# TDA2040_Amp_v1_4.net
KiCad netlist of a schematic drawn in EAGLE
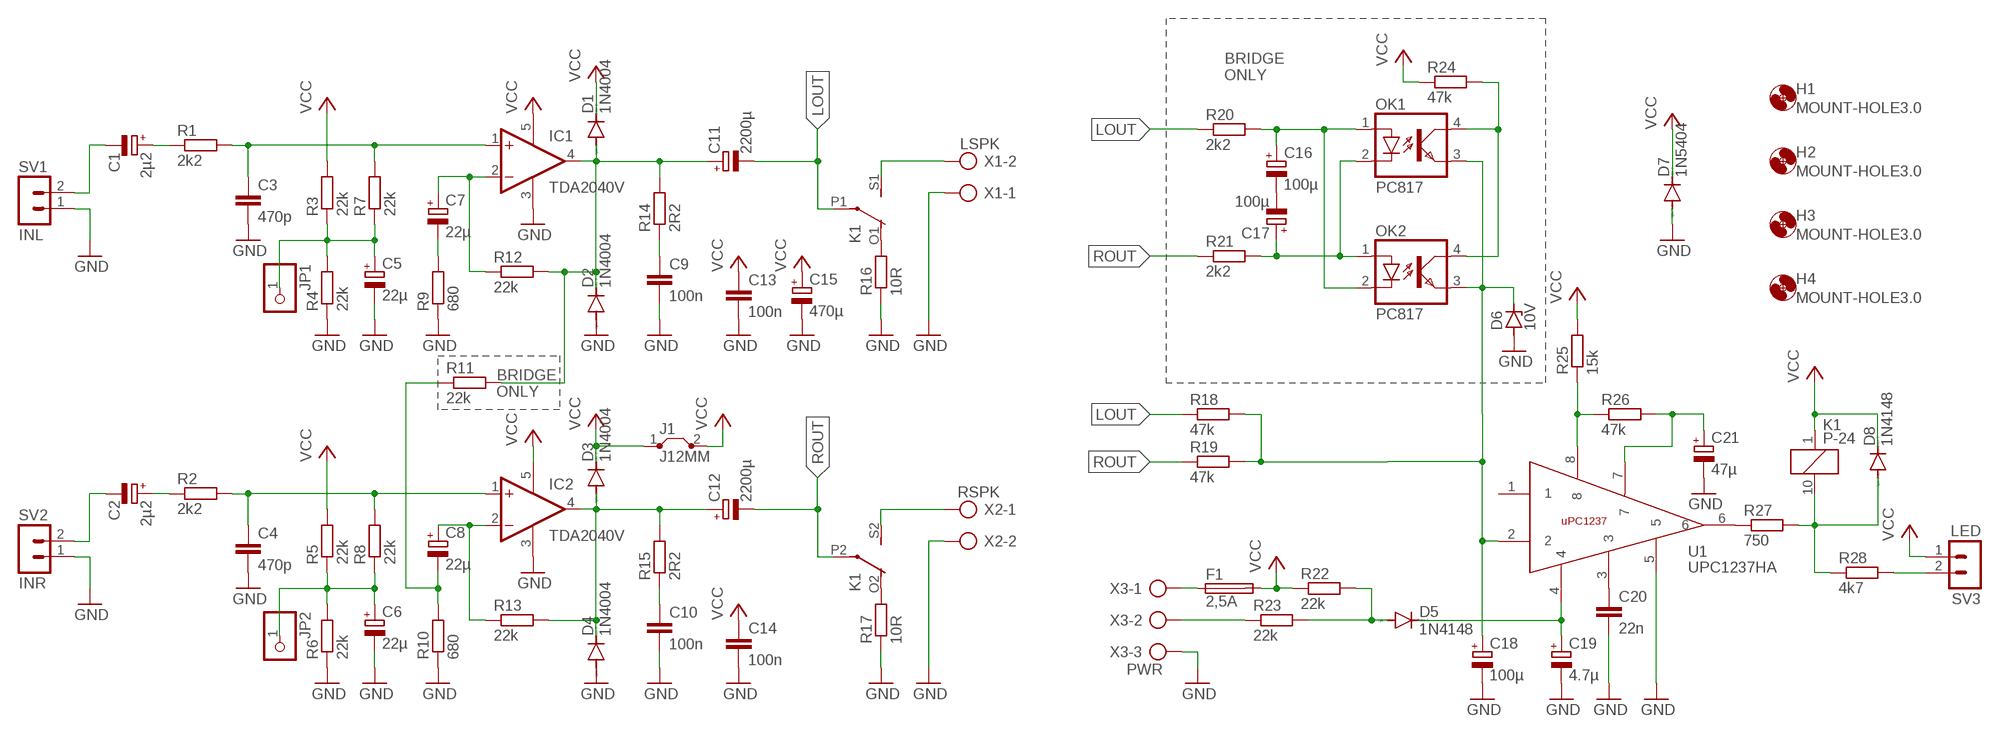
[diagram p0: schematic, sheet 1]

(export (version "E")
  (design (tool "Eeschema 10.0.6"))
  (components
    (comp (ref "C1")
      (value "2µ2")
      (footprint "eagle-import:E2,5-5")
      (libsource (lib "eagle-import") (part "CPOL-EUE2.5-5"))
    )
    (comp (ref "C2")
      (value "2µ2")
      (footprint "eagle-import:E2,5-5")
      (libsource (lib "eagle-import") (part "CPOL-EUE2.5-5"))
    )
    (comp (ref "C3")
      (value "470p")
      (footprint "eagle-import:C050-024X044")
      (libsource (lib "eagle-import") (part "C-EU050-024X044"))
    )
    (comp (ref "C4")
      (value "470p")
      (footprint "eagle-import:C050-024X044")
      (libsource (lib "eagle-import") (part "C-EU050-024X044"))
    )
    (comp (ref "C5")
      (value "22µ")
      (footprint "eagle-import:E2,5-6")
      (libsource (lib "eagle-import") (part "CPOL-EUE2.5-6"))
    )
    (comp (ref "C6")
      (value "22µ")
      (footprint "eagle-import:E2,5-6")
      (libsource (lib "eagle-import") (part "CPOL-EUE2.5-6"))
    )
    (comp (ref "C7")
      (value "22µ")
      (footprint "eagle-import:E2,5-6")
      (libsource (lib "eagle-import") (part "CPOL-EUE2.5-6"))
    )
    (comp (ref "C8")
      (value "22µ")
      (footprint "eagle-import:E2,5-6")
      (libsource (lib "eagle-import") (part "CPOL-EUE2.5-6"))
    )
    (comp (ref "C9")
      (value "100n")
      (footprint "eagle-import:C050-024X044")
      (libsource (lib "eagle-import") (part "C-EU050-024X044"))
    )
    (comp (ref "C10")
      (value "100n")
      (footprint "eagle-import:C050-024X044")
      (libsource (lib "eagle-import") (part "C-EU050-024X044"))
    )
    (comp (ref "C11")
      (value "2200µ")
      (footprint "eagle-import:E5-13")
      (libsource (lib "eagle-import") (part "CPOL-EUE5-13"))
    )
    (comp (ref "C12")
      (value "2200µ")
      (footprint "eagle-import:E5-13")
      (libsource (lib "eagle-import") (part "CPOL-EUE5-13"))
    )
    (comp (ref "C13")
      (value "100n")
      (footprint "eagle-import:C050-024X044")
      (libsource (lib "eagle-import") (part "C-EU050-024X044"))
    )
    (comp (ref "C14")
      (value "100n")
      (footprint "eagle-import:C050-024X044")
      (libsource (lib "eagle-import") (part "C-EU050-024X044"))
    )
    (comp (ref "C15")
      (value "470µ")
      (footprint "eagle-import:E5-13")
      (libsource (lib "eagle-import") (part "CPOL-EUE5-13"))
    )
    (comp (ref "C16")
      (value "100µ")
      (footprint "eagle-import:E2,5-6")
      (libsource (lib "eagle-import") (part "CPOL-EUE2.5-6"))
    )
    (comp (ref "C17")
      (value "100µ")
      (footprint "eagle-import:E2,5-6")
      (libsource (lib "eagle-import") (part "CPOL-EUE2.5-6"))
    )
    (comp (ref "C18")
      (value "100µ")
      (footprint "eagle-import:E2,5-5")
      (libsource (lib "eagle-import") (part "CPOL-EUE2.5-5"))
    )
    (comp (ref "C19")
      (value "4.7µ")
      (footprint "eagle-import:E2,5-5")
      (libsource (lib "eagle-import") (part "CPOL-EUE2.5-5"))
    )
    (comp (ref "C20")
      (value "22n")
      (footprint "eagle-import:C050-024X044")
      (libsource (lib "eagle-import") (part "C-EU050-024X044"))
    )
    (comp (ref "C21")
      (value "47µ")
      (footprint "eagle-import:E2,5-5")
      (libsource (lib "eagle-import") (part "CPOL-EUE2.5-5"))
    )
    (comp (ref "D1")
      (value "1N4004")
      (footprint "eagle-import:DO41-10")
      (libsource (lib "eagle-import") (part "1N4004"))
    )
    (comp (ref "D2")
      (value "1N4004")
      (footprint "eagle-import:DO41-10")
      (libsource (lib "eagle-import") (part "1N4004"))
    )
    (comp (ref "D3")
      (value "1N4004")
      (footprint "eagle-import:DO41-10")
      (libsource (lib "eagle-import") (part "1N4004"))
    )
    (comp (ref "D4")
      (value "1N4004")
      (footprint "eagle-import:DO41-10")
      (libsource (lib "eagle-import") (part "1N4004"))
    )
    (comp (ref "D5")
      (value "1N4148")
      (footprint "eagle-import:DO35-7")
      (libsource (lib "eagle-import") (part "1N4148DO35-7"))
    )
    (comp (ref "D6")
      (value "10V")
      (footprint "eagle-import:DO34Z7")
      (libsource (lib "eagle-import") (part "ZENER-DIODEDO34-7"))
    )
    (comp (ref "D7")
      (value "1N5404")
      (footprint "eagle-import:DO201-15")
      (libsource (lib "eagle-import") (part "1N5400"))
    )
    (comp (ref "D8")
      (value "1N4148")
      (footprint "eagle-import:DO35-7")
      (libsource (lib "eagle-import") (part "1N4148DO35-7"))
    )
    (comp (ref "F1")
      (value "2,5A")
      (footprint "eagle-import:SH22")
      (libsource (lib "eagle-import") (part "SH22"))
    )
    (comp (ref "H1")
      (value "MOUNT-HOLE3.0")
      (footprint "eagle-import:3,0")
      (libsource (lib "eagle-import") (part "MOUNT-HOLE3.0"))
    )
    (comp (ref "H2")
      (value "MOUNT-HOLE3.0")
      (footprint "eagle-import:3,0")
      (libsource (lib "eagle-import") (part "MOUNT-HOLE3.0"))
    )
    (comp (ref "H3")
      (value "MOUNT-HOLE3.0")
      (footprint "eagle-import:3,0")
      (libsource (lib "eagle-import") (part "MOUNT-HOLE3.0"))
    )
    (comp (ref "H4")
      (value "MOUNT-HOLE3.0")
      (footprint "eagle-import:3,0")
      (libsource (lib "eagle-import") (part "MOUNT-HOLE3.0"))
    )
    (comp (ref "IC1")
      (value "TDA2040V")
      (footprint "eagle-import:CB360")
      (libsource (lib "eagle-import") (part "TDA2040V"))
    )
    (comp (ref "IC2")
      (value "TDA2040V")
      (footprint "eagle-import:CB360")
      (libsource (lib "eagle-import") (part "TDA2040V"))
    )
    (comp (ref "J1")
      (value "J12MM")
      (footprint "eagle-import:12")
      (libsource (lib "eagle-import") (part "J12MM"))
    )
    (comp (ref "JP1")
      (value "PINHD-1X1A")
      (footprint "eagle-import:1X01A")
      (libsource (lib "eagle-import") (part "PINHD-1X1A"))
    )
    (comp (ref "JP2")
      (value "PINHD-1X1A")
      (footprint "eagle-import:1X01A")
      (libsource (lib "eagle-import") (part "PINHD-1X1A"))
    )
    (comp (ref "K1")
      (value "P-24")
      (footprint "eagle-import:G6H2-100")
      (libsource (lib "eagle-import") (part "G6H2-100"))
    )
    (comp (ref "OK1")
      (value "PC817")
      (footprint "eagle-import:DIL04")
      (fields (field (name "MPN") "PC817X4J000F"))
      (libsource (lib "eagle-import") (part "PC817"))
    )
    (comp (ref "OK2")
      (value "PC817")
      (footprint "eagle-import:DIL04")
      (fields (field (name "MPN") "PC817X4J000F"))
      (libsource (lib "eagle-import") (part "PC817"))
    )
    (comp (ref "R1")
      (value "2k2")
      (footprint "eagle-import:0207_10")
      (libsource (lib "eagle-import") (part "R-EU_0207/10"))
    )
    (comp (ref "R2")
      (value "2k2")
      (footprint "eagle-import:0207_10")
      (libsource (lib "eagle-import") (part "R-EU_0207/10"))
    )
    (comp (ref "R3")
      (value "22k")
      (footprint "eagle-import:0207_10")
      (libsource (lib "eagle-import") (part "R-EU_0207/10"))
    )
    (comp (ref "R4")
      (value "22k")
      (footprint "eagle-import:0207_10")
      (libsource (lib "eagle-import") (part "R-EU_0207/10"))
    )
    (comp (ref "R5")
      (value "22k")
      (footprint "eagle-import:0207_10")
      (libsource (lib "eagle-import") (part "R-EU_0207/10"))
    )
    (comp (ref "R6")
      (value "22k")
      (footprint "eagle-import:0207_10")
      (libsource (lib "eagle-import") (part "R-EU_0207/10"))
    )
    (comp (ref "R7")
      (value "22k")
      (footprint "eagle-import:0207_10")
      (libsource (lib "eagle-import") (part "R-EU_0207/10"))
    )
    (comp (ref "R8")
      (value "22k")
      (footprint "eagle-import:0207_10")
      (libsource (lib "eagle-import") (part "R-EU_0207/10"))
    )
    (comp (ref "R9")
      (value "680")
      (footprint "eagle-import:0207_10")
      (libsource (lib "eagle-import") (part "R-EU_0207/10"))
    )
    (comp (ref "R10")
      (value "680")
      (footprint "eagle-import:0207_10")
      (libsource (lib "eagle-import") (part "R-EU_0207/10"))
    )
    (comp (ref "R11")
      (value "22k")
      (footprint "eagle-import:0207_10")
      (libsource (lib "eagle-import") (part "R-EU_0207/10"))
    )
    (comp (ref "R12")
      (value "22k")
      (footprint "eagle-import:0207_10")
      (libsource (lib "eagle-import") (part "R-EU_0207/10"))
    )
    (comp (ref "R13")
      (value "22k")
      (footprint "eagle-import:0207_10")
      (libsource (lib "eagle-import") (part "R-EU_0207/10"))
    )
    (comp (ref "R14")
      (value "2R2")
      (footprint "eagle-import:0207_10")
      (libsource (lib "eagle-import") (part "R-EU_0207/10"))
    )
    (comp (ref "R15")
      (value "2R2")
      (footprint "eagle-import:0207_10")
      (libsource (lib "eagle-import") (part "R-EU_0207/10"))
    )
    (comp (ref "R16")
      (value "10R")
      (footprint "eagle-import:0207_10")
      (libsource (lib "eagle-import") (part "R-EU_0207/10"))
    )
    (comp (ref "R17")
      (value "10R")
      (footprint "eagle-import:0207_10")
      (libsource (lib "eagle-import") (part "R-EU_0207/10"))
    )
    (comp (ref "R18")
      (value "47k")
      (footprint "eagle-import:0207_10")
      (libsource (lib "eagle-import") (part "R-EU_0207/10"))
    )
    (comp (ref "R19")
      (value "47k")
      (footprint "eagle-import:0207_10")
      (libsource (lib "eagle-import") (part "R-EU_0207/10"))
    )
    (comp (ref "R20")
      (value "2k2")
      (footprint "eagle-import:0207_10")
      (libsource (lib "eagle-import") (part "R-EU_0207/10"))
    )
    (comp (ref "R21")
      (value "2k2")
      (footprint "eagle-import:0207_10")
      (libsource (lib "eagle-import") (part "R-EU_0207/10"))
    )
    (comp (ref "R22")
      (value "22k")
      (footprint "eagle-import:0207_10")
      (libsource (lib "eagle-import") (part "R-EU_0207/10"))
    )
    (comp (ref "R23")
      (value "22k")
      (footprint "eagle-import:0207_10")
      (libsource (lib "eagle-import") (part "R-EU_0207/10"))
    )
    (comp (ref "R24")
      (value "47k")
      (footprint "eagle-import:0207_10")
      (libsource (lib "eagle-import") (part "R-EU_0207/10"))
    )
    (comp (ref "R25")
      (value "15k")
      (footprint "eagle-import:0207_10")
      (libsource (lib "eagle-import") (part "R-EU_0207/10"))
    )
    (comp (ref "R26")
      (value "47k")
      (footprint "eagle-import:0207_10")
      (libsource (lib "eagle-import") (part "R-EU_0207/10"))
    )
    (comp (ref "R27")
      (value "750")
      (footprint "eagle-import:0207_10")
      (libsource (lib "eagle-import") (part "R-EU_0207/10"))
    )
    (comp (ref "R28")
      (value "4k7")
      (footprint "eagle-import:0207_10")
      (libsource (lib "eagle-import") (part "R-EU_0207/10"))
    )
    (comp (ref "SV1")
      (value "INL")
      (footprint "eagle-import:MA02-1")
      (libsource (lib "eagle-import") (part "MA02-1"))
    )
    (comp (ref "SV2")
      (value "INR")
      (footprint "eagle-import:MA02-1")
      (libsource (lib "eagle-import") (part "MA02-1"))
    )
    (comp (ref "SV3")
      (value "LED")
      (footprint "eagle-import:MA02-1")
      (libsource (lib "eagle-import") (part "MA02-1"))
    )
    (comp (ref "U1")
      (value "UPC1237HA")
      (footprint "eagle-import:SIP8")
      (fields (field (name "MF") "NEC"))
      (libsource (lib "eagle-import") (part "UPC1237HA"))
    )
    (comp (ref "X1")
      (value "LSPK")
      (footprint "eagle-import:AK500_2")
      (libsource (lib "eagle-import") (part "AK500/2"))
    )
    (comp (ref "X2")
      (value "RSPK")
      (footprint "eagle-import:AK500_2")
      (libsource (lib "eagle-import") (part "AK500/2"))
    )
    (comp (ref "X3")
      (value "PWR")
      (footprint "eagle-import:AK500_3")
      (libsource (lib "eagle-import") (part "AK500/3"))
    )
  )
  (nets
    (net (code "1") (name "GND") (class "Default")
      (node (ref "C10") (pin "2") (pinfunction "2_2") (pintype "passive"))
      (node (ref "C13") (pin "2") (pinfunction "2_2") (pintype "passive"))
      (node (ref "C14") (pin "2") (pinfunction "2_2") (pintype "passive"))
      (node (ref "C15") (pin "-") (pinfunction "-_-") (pintype "passive"))
      (node (ref "C18") (pin "-") (pinfunction "-_-") (pintype "passive"))
      (node (ref "C19") (pin "-") (pinfunction "-_-") (pintype "passive"))
      (node (ref "C20") (pin "2") (pinfunction "2_2") (pintype "passive"))
      (node (ref "C21") (pin "-") (pinfunction "-_-") (pintype "passive"))
      (node (ref "C3") (pin "2") (pinfunction "2_2") (pintype "passive"))
      (node (ref "C4") (pin "2") (pinfunction "2_2") (pintype "passive"))
      (node (ref "C5") (pin "-") (pinfunction "-_-") (pintype "passive"))
      (node (ref "C6") (pin "-") (pinfunction "-_-") (pintype "passive"))
      (node (ref "C9") (pin "2") (pinfunction "2_2") (pintype "passive"))
      (node (ref "D2") (pin "A") (pinfunction "A_A") (pintype "passive"))
      (node (ref "D4") (pin "A") (pinfunction "A_A") (pintype "passive"))
      (node (ref "D6") (pin "A") (pinfunction "A_A") (pintype "passive"))
      (node (ref "D7") (pin "A") (pinfunction "A_A") (pintype "passive"))
      (node (ref "IC1") (pin "3") (pinfunction "V-_3") (pintype "power_in"))
      (node (ref "IC2") (pin "3") (pinfunction "V-_3") (pintype "power_in"))
      (node (ref "R10") (pin "1") (pinfunction "1_1") (pintype "passive"))
      (node (ref "R16") (pin "1") (pinfunction "1_1") (pintype "passive"))
      (node (ref "R17") (pin "1") (pinfunction "1_1") (pintype "passive"))
      (node (ref "R4") (pin "1") (pinfunction "1_1") (pintype "passive"))
      (node (ref "R6") (pin "1") (pinfunction "1_1") (pintype "passive"))
      (node (ref "R9") (pin "1") (pinfunction "1_1") (pintype "passive"))
      (node (ref "SV1") (pin "1") (pinfunction "1_1") (pintype "passive"))
      (node (ref "SV2") (pin "1") (pinfunction "1_1") (pintype "passive"))
      (node (ref "U1") (pin "5") (pinfunction "5_5") (pintype "bidirectional"))
      (node (ref "X1") (pin "1") (pinfunction "KL_1") (pintype "passive"))
      (node (ref "X2") (pin "2") (pinfunction "KL_2") (pintype "passive"))
      (node (ref "X3") (pin "3") (pinfunction "KL_3") (pintype "passive"))
    )
    (net (code "2") (name "LOUT") (class "Default")
      (node (ref "C11") (pin "-") (pinfunction "-_-") (pintype "passive"))
      (node (ref "K1") (pin "P1") (pinfunction "P_P1") (pintype "passive"))
      (node (ref "R18") (pin "1") (pinfunction "1_1") (pintype "passive"))
      (node (ref "R20") (pin "1") (pinfunction "1_1") (pintype "passive"))
    )
    (net (code "3") (name "Net-(C1-Pad+)") (class "Default")
      (node (ref "C1") (pin "+") (pinfunction "+_+") (pintype "passive"))
      (node (ref "R1") (pin "1") (pinfunction "1_1") (pintype "passive"))
    )
    (net (code "4") (name "Net-(C1-Pad-)") (class "Default")
      (node (ref "C1") (pin "-") (pinfunction "-_-") (pintype "passive"))
      (node (ref "SV1") (pin "2") (pinfunction "2_2") (pintype "passive"))
    )
    (net (code "5") (name "Net-(C2-Pad+)") (class "Default")
      (node (ref "C2") (pin "+") (pinfunction "+_+") (pintype "passive"))
      (node (ref "R2") (pin "1") (pinfunction "1_1") (pintype "passive"))
    )
    (net (code "6") (name "Net-(C2-Pad-)") (class "Default")
      (node (ref "C2") (pin "-") (pinfunction "-_-") (pintype "passive"))
      (node (ref "SV2") (pin "2") (pinfunction "2_2") (pintype "passive"))
    )
    (net (code "7") (name "Net-(C5-Pad+)") (class "Default")
      (node (ref "C5") (pin "+") (pinfunction "+_+") (pintype "passive"))
      (node (ref "JP1") (pin "1") (pinfunction "1_1") (pintype "passive"))
      (node (ref "R3") (pin "1") (pinfunction "1_1") (pintype "passive"))
      (node (ref "R4") (pin "2") (pinfunction "2_2") (pintype "passive"))
      (node (ref "R7") (pin "1") (pinfunction "1_1") (pintype "passive"))
    )
    (net (code "8") (name "Net-(C6-Pad+)") (class "Default")
      (node (ref "C6") (pin "+") (pinfunction "+_+") (pintype "passive"))
      (node (ref "JP2") (pin "1") (pinfunction "1_1") (pintype "passive"))
      (node (ref "R5") (pin "1") (pinfunction "1_1") (pintype "passive"))
      (node (ref "R6") (pin "2") (pinfunction "2_2") (pintype "passive"))
      (node (ref "R8") (pin "1") (pinfunction "1_1") (pintype "passive"))
    )
    (net (code "9") (name "Net-(C7-Pad-)") (class "Default")
      (node (ref "C7") (pin "-") (pinfunction "-_-") (pintype "passive"))
      (node (ref "R9") (pin "2") (pinfunction "2_2") (pintype "passive"))
    )
    (net (code "10") (name "Net-(C8-Pad-)") (class "Default")
      (node (ref "C8") (pin "-") (pinfunction "-_-") (pintype "passive"))
      (node (ref "R10") (pin "2") (pinfunction "2_2") (pintype "passive"))
      (node (ref "R11") (pin "1") (pinfunction "1_1") (pintype "passive"))
    )
    (net (code "11") (name "Net-(C9-Pad1)") (class "Default")
      (node (ref "C9") (pin "1") (pinfunction "1_1") (pintype "passive"))
      (node (ref "R14") (pin "1") (pinfunction "1_1") (pintype "passive"))
    )
    (net (code "12") (name "Net-(C10-Pad1)") (class "Default")
      (node (ref "C10") (pin "1") (pinfunction "1_1") (pintype "passive"))
      (node (ref "R15") (pin "1") (pinfunction "1_1") (pintype "passive"))
    )
    (net (code "13") (name "Net-(C16-Pad-)") (class "Default")
      (node (ref "C16") (pin "-") (pinfunction "-_-") (pintype "passive"))
      (node (ref "C17") (pin "-") (pinfunction "-_-") (pintype "passive"))
    )
    (net (code "14") (name "Net-(C19-Pad+)") (class "Default")
      (node (ref "C19") (pin "+") (pinfunction "+_+") (pintype "passive"))
      (node (ref "D5") (pin "C") (pinfunction "C_C") (pintype "passive"))
      (node (ref "U1") (pin "4") (pinfunction "4_4") (pintype "bidirectional"))
    )
    (net (code "15") (name "Net-(C20-Pad1)") (class "Default")
      (node (ref "C20") (pin "1") (pinfunction "1_1") (pintype "passive"))
      (node (ref "U1") (pin "3") (pinfunction "3_3") (pintype "bidirectional"))
    )
    (net (code "16") (name "Net-(C21-Pad+)") (class "Default")
      (node (ref "C21") (pin "+") (pinfunction "+_+") (pintype "passive"))
      (node (ref "R26") (pin "2") (pinfunction "2_2") (pintype "passive"))
      (node (ref "U1") (pin "7") (pinfunction "7_7") (pintype "bidirectional"))
    )
    (net (code "17") (name "Net-(D5-PadA)") (class "Default")
      (node (ref "D5") (pin "A") (pinfunction "A_A") (pintype "passive"))
      (node (ref "R22") (pin "2") (pinfunction "2_2") (pintype "passive"))
      (node (ref "R23") (pin "2") (pinfunction "2_2") (pintype "passive"))
    )
    (net (code "18") (name "Net-(IC1-+IN)") (class "Default")
      (node (ref "C3") (pin "1") (pinfunction "1_1") (pintype "passive"))
      (node (ref "IC1") (pin "1") (pinfunction "+IN_1") (pintype "input"))
      (node (ref "R1") (pin "2") (pinfunction "2_2") (pintype "passive"))
      (node (ref "R7") (pin "2") (pinfunction "2_2") (pintype "passive"))
    )
    (net (code "19") (name "Net-(IC1--IN)") (class "Default")
      (node (ref "C7") (pin "+") (pinfunction "+_+") (pintype "passive"))
      (node (ref "IC1") (pin "2") (pinfunction "-IN_2") (pintype "input"))
      (node (ref "R12") (pin "1") (pinfunction "1_1") (pintype "passive"))
    )
    (net (code "20") (name "Net-(IC1-OUT)") (class "Default")
      (node (ref "C11") (pin "+") (pinfunction "+_+") (pintype "passive"))
      (node (ref "D1") (pin "A") (pinfunction "A_A") (pintype "passive"))
      (node (ref "D2") (pin "C") (pinfunction "C_C") (pintype "passive"))
      (node (ref "IC1") (pin "4") (pinfunction "OUT_4") (pintype "output"))
      (node (ref "R11") (pin "2") (pinfunction "2_2") (pintype "passive"))
      (node (ref "R12") (pin "2") (pinfunction "2_2") (pintype "passive"))
      (node (ref "R14") (pin "2") (pinfunction "2_2") (pintype "passive"))
    )
    (net (code "21") (name "Net-(IC2-+IN)") (class "Default")
      (node (ref "C4") (pin "1") (pinfunction "1_1") (pintype "passive"))
      (node (ref "IC2") (pin "1") (pinfunction "+IN_1") (pintype "input"))
      (node (ref "R2") (pin "2") (pinfunction "2_2") (pintype "passive"))
      (node (ref "R8") (pin "2") (pinfunction "2_2") (pintype "passive"))
    )
    (net (code "22") (name "Net-(IC2--IN)") (class "Default")
      (node (ref "C8") (pin "+") (pinfunction "+_+") (pintype "passive"))
      (node (ref "IC2") (pin "2") (pinfunction "-IN_2") (pintype "input"))
      (node (ref "R13") (pin "1") (pinfunction "1_1") (pintype "passive"))
    )
    (net (code "23") (name "Net-(IC2-OUT)") (class "Default")
      (node (ref "C12") (pin "+") (pinfunction "+_+") (pintype "passive"))
      (node (ref "D3") (pin "A") (pinfunction "A_A") (pintype "passive"))
      (node (ref "D4") (pin "C") (pinfunction "C_C") (pintype "passive"))
      (node (ref "IC2") (pin "4") (pinfunction "OUT_4") (pintype "output"))
      (node (ref "R13") (pin "2") (pinfunction "2_2") (pintype "passive"))
      (node (ref "R15") (pin "2") (pinfunction "2_2") (pintype "passive"))
    )
    (net (code "24") (name "Net-(K1A-2)") (class "Default")
      (node (ref "D8") (pin "A") (pinfunction "A_A") (pintype "passive"))
      (node (ref "K1") (pin "10") (pinfunction "2_10") (pintype "passive"))
      (node (ref "R27") (pin "2") (pinfunction "2_2") (pintype "passive"))
      (node (ref "R28") (pin "1") (pinfunction "1_1") (pintype "passive"))
    )
    (net (code "25") (name "Net-(K1B-O)") (class "Default")
      (node (ref "K1") (pin "O1") (pinfunction "O_O1") (pintype "passive"))
      (node (ref "R16") (pin "2") (pinfunction "2_2") (pintype "passive"))
    )
    (net (code "26") (name "Net-(K1B-S)") (class "Default")
      (node (ref "K1") (pin "S1") (pinfunction "S_S1") (pintype "passive"))
      (node (ref "X1") (pin "2") (pinfunction "KL_2") (pintype "passive"))
    )
    (net (code "27") (name "Net-(K1C-O)") (class "Default")
      (node (ref "K1") (pin "O2") (pinfunction "O_O2") (pintype "passive"))
      (node (ref "R17") (pin "2") (pinfunction "2_2") (pintype "passive"))
    )
    (net (code "28") (name "Net-(K1C-S)") (class "Default")
      (node (ref "K1") (pin "S2") (pinfunction "S_S2") (pintype "passive"))
      (node (ref "X2") (pin "1") (pinfunction "KL_1") (pintype "passive"))
    )
    (net (code "29") (name "Net-(OK1-A)") (class "Default")
      (node (ref "C16") (pin "+") (pinfunction "+_+") (pintype "passive"))
      (node (ref "OK1") (pin "1") (pinfunction "A_1") (pintype "passive"))
      (node (ref "OK2") (pin "2") (pinfunction "C_2") (pintype "passive"))
      (node (ref "R20") (pin "2") (pinfunction "2_2") (pintype "passive"))
    )
    (net (code "30") (name "Net-(OK1-C)") (class "Default")
      (node (ref "C17") (pin "+") (pinfunction "+_+") (pintype "passive"))
      (node (ref "OK1") (pin "2") (pinfunction "C_2") (pintype "passive"))
      (node (ref "OK2") (pin "1") (pinfunction "A_1") (pintype "passive"))
      (node (ref "R21") (pin "2") (pinfunction "2_2") (pintype "passive"))
    )
    (net (code "31") (name "Net-(OK1-COL)") (class "Default")
      (node (ref "OK1") (pin "4") (pinfunction "COL_4") (pintype "passive"))
      (node (ref "OK2") (pin "4") (pinfunction "COL_4") (pintype "passive"))
      (node (ref "R24") (pin "2") (pinfunction "2_2") (pintype "passive"))
    )
    (net (code "32") (name "Net-(OK1-EMIT)") (class "Default")
      (node (ref "C18") (pin "+") (pinfunction "+_+") (pintype "passive"))
      (node (ref "D6") (pin "C") (pinfunction "C_C") (pintype "passive"))
      (node (ref "OK1") (pin "3") (pinfunction "EMIT_3") (pintype "passive"))
      (node (ref "OK2") (pin "3") (pinfunction "EMIT_3") (pintype "passive"))
      (node (ref "R18") (pin "2") (pinfunction "2_2") (pintype "passive"))
      (node (ref "R19") (pin "2") (pinfunction "2_2") (pintype "passive"))
      (node (ref "U1") (pin "2") (pinfunction "2_2") (pintype "bidirectional"))
    )
    (net (code "33") (name "Net-(R25-Pad1)") (class "Default")
      (node (ref "R25") (pin "1") (pinfunction "1_1") (pintype "passive"))
      (node (ref "R26") (pin "1") (pinfunction "1_1") (pintype "passive"))
      (node (ref "U1") (pin "8") (pinfunction "8_8") (pintype "bidirectional"))
    )
    (net (code "34") (name "Net-(R27-Pad1)") (class "Default")
      (node (ref "R27") (pin "1") (pinfunction "1_1") (pintype "passive"))
      (node (ref "U1") (pin "6") (pinfunction "6_6") (pintype "bidirectional"))
    )
    (net (code "35") (name "Net-(R28-Pad2)") (class "Default")
      (node (ref "R28") (pin "2") (pinfunction "2_2") (pintype "passive"))
      (node (ref "SV3") (pin "2") (pinfunction "2_2") (pintype "passive"))
    )
    (net (code "36") (name "Net-(X3A-KL)") (class "Default")
      (node (ref "F1") (pin "1") (pinfunction "1_1") (pintype "passive"))
      (node (ref "X3") (pin "1") (pinfunction "KL_1") (pintype "passive"))
    )
    (net (code "37") (name "Net-(X3B-KL)") (class "Default")
      (node (ref "R23") (pin "1") (pinfunction "1_1") (pintype "passive"))
      (node (ref "X3") (pin "2") (pinfunction "KL_2") (pintype "passive"))
    )
    (net (code "38") (name "ROUT") (class "Default")
      (node (ref "C12") (pin "-") (pinfunction "-_-") (pintype "passive"))
      (node (ref "K1") (pin "P2") (pinfunction "P_P2") (pintype "passive"))
      (node (ref "R19") (pin "1") (pinfunction "1_1") (pintype "passive"))
      (node (ref "R21") (pin "1") (pinfunction "1_1") (pintype "passive"))
    )
    (net (code "39") (name "VCC") (class "Default")
      (node (ref "C13") (pin "1") (pinfunction "1_1") (pintype "passive"))
      (node (ref "C14") (pin "1") (pinfunction "1_1") (pintype "passive"))
      (node (ref "C15") (pin "+") (pinfunction "+_+") (pintype "passive"))
      (node (ref "D1") (pin "C") (pinfunction "C_C") (pintype "passive"))
      (node (ref "D3") (pin "C") (pinfunction "C_C") (pintype "passive"))
      (node (ref "D7") (pin "C") (pinfunction "C_C") (pintype "passive"))
      (node (ref "D8") (pin "C") (pinfunction "C_C") (pintype "passive"))
      (node (ref "F1") (pin "2") (pinfunction "2_2") (pintype "passive"))
      (node (ref "IC1") (pin "5") (pinfunction "V+_5") (pintype "power_in"))
      (node (ref "IC2") (pin "5") (pinfunction "V+_5") (pintype "power_in"))
      (node (ref "J1") (pin "1") (pinfunction "1_1") (pintype "passive"))
      (node (ref "J1") (pin "2") (pinfunction "2_2") (pintype "passive"))
      (node (ref "K1") (pin "1") (pinfunction "1_1") (pintype "passive"))
      (node (ref "R22") (pin "1") (pinfunction "1_1") (pintype "passive"))
      (node (ref "R24") (pin "1") (pinfunction "1_1") (pintype "passive"))
      (node (ref "R25") (pin "2") (pinfunction "2_2") (pintype "passive"))
      (node (ref "R3") (pin "2") (pinfunction "2_2") (pintype "passive"))
      (node (ref "R5") (pin "2") (pinfunction "2_2") (pintype "passive"))
      (node (ref "SV3") (pin "1") (pinfunction "1_1") (pintype "passive"))
    )
    (net (code "40") (name "unconnected-(U1-Pad1)") (class "Default")
      (node (ref "U1") (pin "1") (pinfunction "1_1") (pintype "bidirectional"))
    )
  )
)
